# 07.net
KiCad netlist of a schematic drawn in Altium Designer
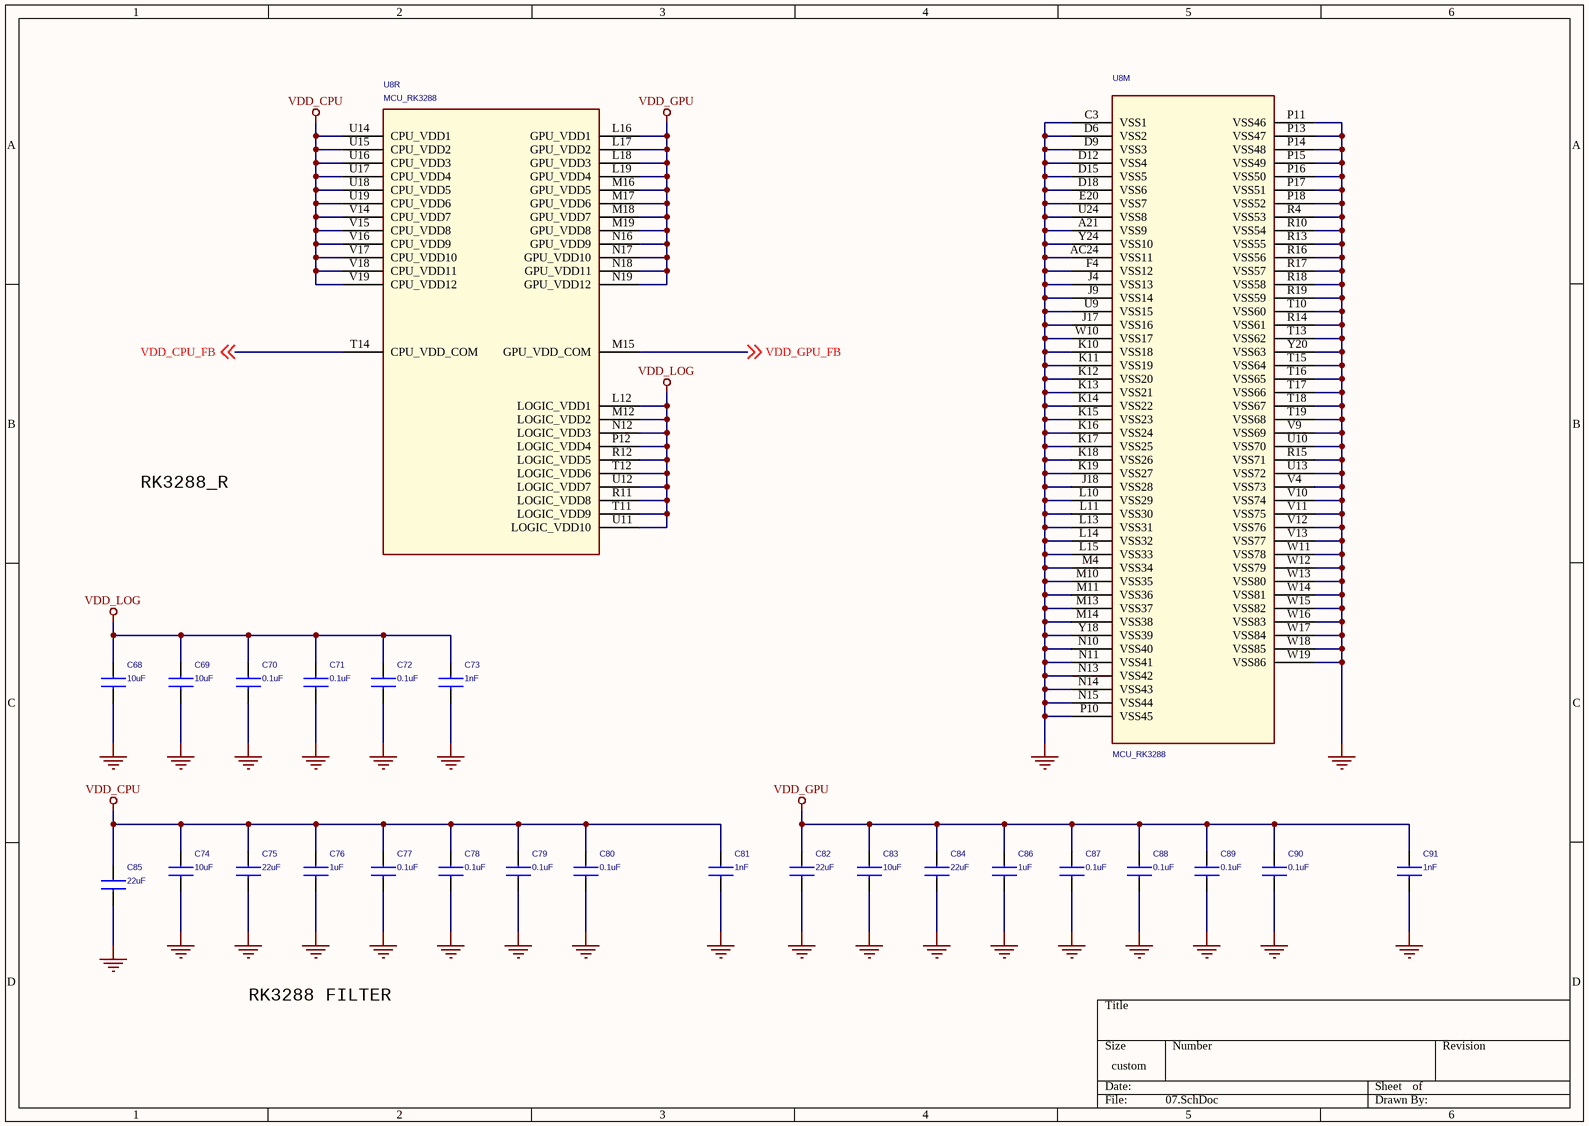
[diagram p0: 07.SchDoc]

(export (version "E")
  (design (tool "Eeschema 10.0.6"))
  (components
    (comp (ref "C68")
      (value "10uF")
      (footprint "C0603")
      (description "CAP,MLCC,10uF,+/-10%,X5R,6.3V,SMD0805")
      (libsource (lib "*") (part "CAP NP_Dup3"))
    )
    (comp (ref "C69") (value "10uF") (footprint "C0603") (libsource (lib "*") (part "CAP NP_Dup3")))
    (comp (ref "C70") (value "0.1uF") (footprint "C0603") (libsource (lib "*") (part "CAP NP_Dup3")))
    (comp (ref "C71") (value "0.1uF") (footprint "C0603") (libsource (lib "*") (part "CAP NP_Dup3")))
    (comp (ref "C72") (value "0.1uF") (footprint "C0603") (libsource (lib "*") (part "CAP NP_Dup3")))
    (comp (ref "C73") (value "1nF") (footprint "C0603") (libsource (lib "*") (part "CAP NP_Dup3")))
    (comp (ref "C74") (value "10uF") (footprint "C0603") (libsource (lib "*") (part "CAP NP_Dup3")))
    (comp (ref "C75") (value "22uF") (footprint "C0603") (libsource (lib "*") (part "CAP NP_Dup3")))
    (comp (ref "C76") (value "1uF") (footprint "C0603") (libsource (lib "*") (part "CAP NP_Dup3")))
    (comp (ref "C77") (value "0.1uF") (footprint "C0603") (libsource (lib "*") (part "CAP NP_Dup3")))
    (comp (ref "C78") (value "0.1uF") (footprint "C0603") (libsource (lib "*") (part "CAP NP_Dup3")))
    (comp (ref "C79") (value "0.1uF") (footprint "C0603") (libsource (lib "*") (part "CAP NP_Dup3")))
    (comp (ref "C80") (value "0.1uF") (footprint "C0603") (libsource (lib "*") (part "CAP NP_Dup3")))
    (comp (ref "C81") (value "1nF") (footprint "C0603") (libsource (lib "*") (part "CAP NP_Dup3")))
    (comp (ref "C82") (value "22uF") (footprint "C0603") (libsource (lib "*") (part "CAP NP_Dup3")))
    (comp (ref "C83")
      (value "10uF")
      (footprint "C0603")
      (description "CAP,MLCC,10uF,+/-10%,X5R,6.3V,SMD0805")
      (libsource (lib "*") (part "CAP NP_Dup3"))
    )
    (comp (ref "C84") (value "22uF") (footprint "C0603") (libsource (lib "*") (part "CAP NP_Dup3")))
    (comp (ref "C85")
      (value "22uF")
      (footprint "C0603")
      (description "CAP,MLCC,47uF,+/-10%,X5R,4V,SMD1210")
      (libsource (lib "*") (part "CAP NP_Dup3"))
    )
    (comp (ref "C86") (value "1uF") (footprint "C0603") (libsource (lib "*") (part "CAP NP_Dup3")))
    (comp (ref "C87") (value "0.1uF") (footprint "C0603") (libsource (lib "*") (part "CAP NP_Dup3")))
    (comp (ref "C88") (value "0.1uF") (footprint "C0603") (libsource (lib "*") (part "CAP NP_Dup3")))
    (comp (ref "C89") (value "0.1uF") (footprint "C0603") (libsource (lib "*") (part "CAP NP_Dup3")))
    (comp (ref "C90") (value "0.1uF") (footprint "C0603") (libsource (lib "*") (part "CAP NP_Dup3")))
    (comp (ref "C91") (value "1nF") (footprint "C0603") (libsource (lib "*") (part "CAP NP_Dup3")))
    (comp (ref "U8")
      (value "MCU_RK3288")
      (footprint "BGA453-19X19")
      (libsource (lib "*") (part "MCU_RK3288_3"))
    )
  )
  (nets
    (net (code "1") (name "GND") (class "Default")
      (node (ref "C68") (pin "1") (pinfunction "1_1") (pintype "passive"))
      (node (ref "C69") (pin "2") (pinfunction "2_2") (pintype "passive"))
      (node (ref "C70") (pin "2") (pinfunction "2_2") (pintype "passive"))
      (node (ref "C71") (pin "2") (pinfunction "2_2") (pintype "passive"))
      (node (ref "C72") (pin "2") (pinfunction "2_2") (pintype "passive"))
      (node (ref "C73") (pin "2") (pinfunction "2_2") (pintype "passive"))
      (node (ref "C74") (pin "1") (pinfunction "1_1") (pintype "passive"))
      (node (ref "C75") (pin "1") (pinfunction "1_1") (pintype "passive"))
      (node (ref "C76") (pin "2") (pinfunction "2_2") (pintype "passive"))
      (node (ref "C77") (pin "2") (pinfunction "2_2") (pintype "passive"))
      (node (ref "C78") (pin "2") (pinfunction "2_2") (pintype "passive"))
      (node (ref "C79") (pin "2") (pinfunction "2_2") (pintype "passive"))
      (node (ref "C80") (pin "2") (pinfunction "2_2") (pintype "passive"))
      (node (ref "C81") (pin "2") (pinfunction "2_2") (pintype "passive"))
      (node (ref "C82") (pin "1") (pinfunction "1_1") (pintype "passive"))
      (node (ref "C83") (pin "1") (pinfunction "1_1") (pintype "passive"))
      (node (ref "C84") (pin "1") (pinfunction "1_1") (pintype "passive"))
      (node (ref "C85") (pin "2") (pinfunction "2_2") (pintype "passive"))
      (node (ref "C86") (pin "2") (pinfunction "2_2") (pintype "passive"))
      (node (ref "C87") (pin "2") (pinfunction "2_2") (pintype "passive"))
      (node (ref "C88") (pin "2") (pinfunction "2_2") (pintype "passive"))
      (node (ref "C89") (pin "2") (pinfunction "2_2") (pintype "passive"))
      (node (ref "C90") (pin "2") (pinfunction "2_2") (pintype "passive"))
      (node (ref "C91") (pin "2") (pinfunction "2_2") (pintype "passive"))
      (node (ref "U8") (pin "A21") (pinfunction "VSS9_A21") (pintype "power_in"))
      (node (ref "U8") (pin "AC24") (pinfunction "VSS11_AC24") (pintype "power_in"))
      (node (ref "U8") (pin "C3") (pinfunction "VSS1_C3") (pintype "power_in"))
      (node (ref "U8") (pin "D12") (pinfunction "VSS4_D12") (pintype "power_in"))
      (node (ref "U8") (pin "D15") (pinfunction "VSS5_D15") (pintype "power_in"))
      (node (ref "U8") (pin "D18") (pinfunction "VSS6_D18") (pintype "power_in"))
      (node (ref "U8") (pin "D6") (pinfunction "VSS2_D6") (pintype "power_in"))
      (node (ref "U8") (pin "D9") (pinfunction "VSS3_D9") (pintype "power_in"))
      (node (ref "U8") (pin "E20") (pinfunction "VSS7_E20") (pintype "power_in"))
      (node (ref "U8") (pin "F4") (pinfunction "VSS12_F4") (pintype "power_in"))
      (node (ref "U8") (pin "J17") (pinfunction "VSS16_J17") (pintype "power_in"))
      (node (ref "U8") (pin "J18") (pinfunction "VSS28_J18") (pintype "power_in"))
      (node (ref "U8") (pin "J4") (pinfunction "VSS13_J4") (pintype "power_in"))
      (node (ref "U8") (pin "J9") (pinfunction "VSS14_J9") (pintype "power_in"))
      (node (ref "U8") (pin "K10") (pinfunction "VSS18_K10") (pintype "power_in"))
      (node (ref "U8") (pin "K11") (pinfunction "VSS19_K11") (pintype "power_in"))
      (node (ref "U8") (pin "K12") (pinfunction "VSS20_K12") (pintype "power_in"))
      (node (ref "U8") (pin "K13") (pinfunction "VSS21_K13") (pintype "power_in"))
      (node (ref "U8") (pin "K14") (pinfunction "VSS22_K14") (pintype "power_in"))
      (node (ref "U8") (pin "K15") (pinfunction "VSS23_K15") (pintype "power_in"))
      (node (ref "U8") (pin "K16") (pinfunction "VSS24_K16") (pintype "power_in"))
      (node (ref "U8") (pin "K17") (pinfunction "VSS25_K17") (pintype "power_in"))
      (node (ref "U8") (pin "K18") (pinfunction "VSS26_K18") (pintype "power_in"))
      (node (ref "U8") (pin "K19") (pinfunction "VSS27_K19") (pintype "power_in"))
      (node (ref "U8") (pin "L10") (pinfunction "VSS29_L10") (pintype "power_in"))
      (node (ref "U8") (pin "L11") (pinfunction "VSS30_L11") (pintype "power_in"))
      (node (ref "U8") (pin "L13") (pinfunction "VSS31_L13") (pintype "power_in"))
      (node (ref "U8") (pin "L14") (pinfunction "VSS32_L14") (pintype "power_in"))
      (node (ref "U8") (pin "L15") (pinfunction "VSS33_L15") (pintype "power_in"))
      (node (ref "U8") (pin "M10") (pinfunction "VSS35_M10") (pintype "power_in"))
      (node (ref "U8") (pin "M11") (pinfunction "VSS36_M11") (pintype "power_in"))
      (node (ref "U8") (pin "M13") (pinfunction "VSS37_M13") (pintype "power_in"))
      (node (ref "U8") (pin "M14") (pinfunction "VSS38_M14") (pintype "power_in"))
      (node (ref "U8") (pin "M4") (pinfunction "VSS34_M4") (pintype "power_in"))
      (node (ref "U8") (pin "N10") (pinfunction "VSS40_N10") (pintype "power_in"))
      (node (ref "U8") (pin "N11") (pinfunction "VSS41_N11") (pintype "power_in"))
      (node (ref "U8") (pin "N13") (pinfunction "VSS42_N13") (pintype "power_in"))
      (node (ref "U8") (pin "N14") (pinfunction "VSS43_N14") (pintype "power_in"))
      (node (ref "U8") (pin "N15") (pinfunction "VSS44_N15") (pintype "power_in"))
      (node (ref "U8") (pin "P10") (pinfunction "VSS45_P10") (pintype "power_in"))
      (node (ref "U8") (pin "P11") (pinfunction "VSS46_P11") (pintype "power_in"))
      (node (ref "U8") (pin "P13") (pinfunction "VSS47_P13") (pintype "power_in"))
      (node (ref "U8") (pin "P14") (pinfunction "VSS48_P14") (pintype "power_in"))
      (node (ref "U8") (pin "P15") (pinfunction "VSS49_P15") (pintype "power_in"))
      (node (ref "U8") (pin "P16") (pinfunction "VSS50_P16") (pintype "power_in"))
      (node (ref "U8") (pin "P17") (pinfunction "VSS51_P17") (pintype "power_in"))
      (node (ref "U8") (pin "P18") (pinfunction "VSS52_P18") (pintype "power_in"))
      (node (ref "U8") (pin "R10") (pinfunction "VSS54_R10") (pintype "power_in"))
      (node (ref "U8") (pin "R13") (pinfunction "VSS55_R13") (pintype "power_in"))
      (node (ref "U8") (pin "R14") (pinfunction "VSS61_R14") (pintype "power_in"))
      (node (ref "U8") (pin "R15") (pinfunction "VSS71_R15") (pintype "power_in"))
      (node (ref "U8") (pin "R16") (pinfunction "VSS56_R16") (pintype "power_in"))
      (node (ref "U8") (pin "R17") (pinfunction "VSS57_R17") (pintype "power_in"))
      (node (ref "U8") (pin "R18") (pinfunction "VSS58_R18") (pintype "power_in"))
      (node (ref "U8") (pin "R19") (pinfunction "VSS59_R19") (pintype "power_in"))
      (node (ref "U8") (pin "R4") (pinfunction "VSS53_R4") (pintype "power_in"))
      (node (ref "U8") (pin "T10") (pinfunction "VSS60_T10") (pintype "power_in"))
      (node (ref "U8") (pin "T13") (pinfunction "VSS62_T13") (pintype "power_in"))
      (node (ref "U8") (pin "T15") (pinfunction "VSS64_T15") (pintype "power_in"))
      (node (ref "U8") (pin "T16") (pinfunction "VSS65_T16") (pintype "power_in"))
      (node (ref "U8") (pin "T17") (pinfunction "VSS66_T17") (pintype "power_in"))
      (node (ref "U8") (pin "T18") (pinfunction "VSS67_T18") (pintype "power_in"))
      (node (ref "U8") (pin "T19") (pinfunction "VSS68_T19") (pintype "power_in"))
      (node (ref "U8") (pin "U10") (pinfunction "VSS70_U10") (pintype "power_in"))
      (node (ref "U8") (pin "U13") (pinfunction "VSS72_U13") (pintype "power_in"))
      (node (ref "U8") (pin "U24") (pinfunction "VSS8_U24") (pintype "power_in"))
      (node (ref "U8") (pin "U9") (pinfunction "VSS15_U9") (pintype "power_in"))
      (node (ref "U8") (pin "V10") (pinfunction "VSS74_V10") (pintype "power_in"))
      (node (ref "U8") (pin "V11") (pinfunction "VSS75_V11") (pintype "power_in"))
      (node (ref "U8") (pin "V12") (pinfunction "VSS76_V12") (pintype "power_in"))
      (node (ref "U8") (pin "V13") (pinfunction "VSS77_V13") (pintype "power_in"))
      (node (ref "U8") (pin "V4") (pinfunction "VSS73_V4") (pintype "power_in"))
      (node (ref "U8") (pin "V9") (pinfunction "VSS69_V9") (pintype "power_in"))
      (node (ref "U8") (pin "W10") (pinfunction "VSS17_W10") (pintype "power_in"))
      (node (ref "U8") (pin "W11") (pinfunction "VSS78_W11") (pintype "power_in"))
      (node (ref "U8") (pin "W12") (pinfunction "VSS79_W12") (pintype "power_in"))
      (node (ref "U8") (pin "W13") (pinfunction "VSS80_W13") (pintype "power_in"))
      (node (ref "U8") (pin "W14") (pinfunction "VSS81_W14") (pintype "power_in"))
      (node (ref "U8") (pin "W15") (pinfunction "VSS82_W15") (pintype "power_in"))
      (node (ref "U8") (pin "W16") (pinfunction "VSS83_W16") (pintype "power_in"))
      (node (ref "U8") (pin "W17") (pinfunction "VSS84_W17") (pintype "power_in"))
      (node (ref "U8") (pin "W18") (pinfunction "VSS85_W18") (pintype "power_in"))
      (node (ref "U8") (pin "W19") (pinfunction "VSS86_W19") (pintype "power_in"))
      (node (ref "U8") (pin "Y18") (pinfunction "VSS39_Y18") (pintype "power_in"))
      (node (ref "U8") (pin "Y20") (pinfunction "VSS63_Y20") (pintype "power_in"))
      (node (ref "U8") (pin "Y24") (pinfunction "VSS10_Y24") (pintype "power_in"))
    )
    (net (code "2") (name "VDD_CPU") (class "Default")
      (node (ref "C74") (pin "2") (pinfunction "2_2") (pintype "passive"))
      (node (ref "C75") (pin "2") (pinfunction "2_2") (pintype "passive"))
      (node (ref "C76") (pin "1") (pinfunction "1_1") (pintype "passive"))
      (node (ref "C77") (pin "1") (pinfunction "1_1") (pintype "passive"))
      (node (ref "C78") (pin "1") (pinfunction "1_1") (pintype "passive"))
      (node (ref "C79") (pin "1") (pinfunction "1_1") (pintype "passive"))
      (node (ref "C80") (pin "1") (pinfunction "1_1") (pintype "passive"))
      (node (ref "C81") (pin "1") (pinfunction "1_1") (pintype "passive"))
      (node (ref "C85") (pin "1") (pinfunction "1_1") (pintype "passive"))
      (node (ref "U8") (pin "U14") (pinfunction "CPU_VDD1_U14") (pintype "power_in"))
      (node (ref "U8") (pin "U15") (pinfunction "CPU_VDD2_U15") (pintype "power_in"))
      (node (ref "U8") (pin "U16") (pinfunction "CPU_VDD3_U16") (pintype "power_in"))
      (node (ref "U8") (pin "U17") (pinfunction "CPU_VDD4_U17") (pintype "power_in"))
      (node (ref "U8") (pin "U18") (pinfunction "CPU_VDD5_U18") (pintype "power_in"))
      (node (ref "U8") (pin "U19") (pinfunction "CPU_VDD6_U19") (pintype "power_in"))
      (node (ref "U8") (pin "V14") (pinfunction "CPU_VDD7_V14") (pintype "power_in"))
      (node (ref "U8") (pin "V15") (pinfunction "CPU_VDD8_V15") (pintype "power_in"))
      (node (ref "U8") (pin "V16") (pinfunction "CPU_VDD9_V16") (pintype "power_in"))
      (node (ref "U8") (pin "V17") (pinfunction "CPU_VDD10_V17") (pintype "power_in"))
      (node (ref "U8") (pin "V18") (pinfunction "CPU_VDD11_V18") (pintype "power_in"))
      (node (ref "U8") (pin "V19") (pinfunction "CPU_VDD12_V19") (pintype "power_in"))
    )
    (net (code "3") (name "VDD_CPU_FB") (class "Default")
      (node (ref "U8") (pin "T14") (pinfunction "CPU_VDD_COM_T14") (pintype "passive"))
    )
    (net (code "4") (name "VDD_GPU") (class "Default")
      (node (ref "C82") (pin "2") (pinfunction "2_2") (pintype "passive"))
      (node (ref "C83") (pin "2") (pinfunction "2_2") (pintype "passive"))
      (node (ref "C84") (pin "2") (pinfunction "2_2") (pintype "passive"))
      (node (ref "C86") (pin "1") (pinfunction "1_1") (pintype "passive"))
      (node (ref "C87") (pin "1") (pinfunction "1_1") (pintype "passive"))
      (node (ref "C88") (pin "1") (pinfunction "1_1") (pintype "passive"))
      (node (ref "C89") (pin "1") (pinfunction "1_1") (pintype "passive"))
      (node (ref "C90") (pin "1") (pinfunction "1_1") (pintype "passive"))
      (node (ref "C91") (pin "1") (pinfunction "1_1") (pintype "passive"))
      (node (ref "U8") (pin "L16") (pinfunction "GPU_VDD1_L16") (pintype "power_in"))
      (node (ref "U8") (pin "L17") (pinfunction "GPU_VDD2_L17") (pintype "power_in"))
      (node (ref "U8") (pin "L18") (pinfunction "GPU_VDD3_L18") (pintype "power_in"))
      (node (ref "U8") (pin "L19") (pinfunction "GPU_VDD4_L19") (pintype "power_in"))
      (node (ref "U8") (pin "M16") (pinfunction "GPU_VDD5_M16") (pintype "power_in"))
      (node (ref "U8") (pin "M17") (pinfunction "GPU_VDD6_M17") (pintype "power_in"))
      (node (ref "U8") (pin "M18") (pinfunction "GPU_VDD7_M18") (pintype "power_in"))
      (node (ref "U8") (pin "M19") (pinfunction "GPU_VDD8_M19") (pintype "power_in"))
      (node (ref "U8") (pin "N16") (pinfunction "GPU_VDD9_N16") (pintype "power_in"))
      (node (ref "U8") (pin "N17") (pinfunction "GPU_VDD10_N17") (pintype "power_in"))
      (node (ref "U8") (pin "N18") (pinfunction "GPU_VDD11_N18") (pintype "power_in"))
      (node (ref "U8") (pin "N19") (pinfunction "GPU_VDD12_N19") (pintype "power_in"))
    )
    (net (code "5") (name "VDD_GPU_FB") (class "Default")
      (node (ref "U8") (pin "M15") (pinfunction "GPU_VDD_COM_M15") (pintype "passive"))
    )
    (net (code "6") (name "VDD_LOG") (class "Default")
      (node (ref "C68") (pin "2") (pinfunction "2_2") (pintype "passive"))
      (node (ref "C69") (pin "1") (pinfunction "1_1") (pintype "passive"))
      (node (ref "C70") (pin "1") (pinfunction "1_1") (pintype "passive"))
      (node (ref "C71") (pin "1") (pinfunction "1_1") (pintype "passive"))
      (node (ref "C72") (pin "1") (pinfunction "1_1") (pintype "passive"))
      (node (ref "C73") (pin "1") (pinfunction "1_1") (pintype "passive"))
      (node (ref "U8") (pin "L12") (pinfunction "LOGIC_VDD1_L12") (pintype "power_in"))
      (node (ref "U8") (pin "M12") (pinfunction "LOGIC_VDD2_M12") (pintype "power_in"))
      (node (ref "U8") (pin "N12") (pinfunction "LOGIC_VDD3_N12") (pintype "power_in"))
      (node (ref "U8") (pin "P12") (pinfunction "LOGIC_VDD4_P12") (pintype "power_in"))
      (node (ref "U8") (pin "R11") (pinfunction "LOGIC_VDD8_R11") (pintype "power_in"))
      (node (ref "U8") (pin "R12") (pinfunction "LOGIC_VDD5_R12") (pintype "power_in"))
      (node (ref "U8") (pin "T11") (pinfunction "LOGIC_VDD9_T11") (pintype "power_in"))
      (node (ref "U8") (pin "T12") (pinfunction "LOGIC_VDD6_T12") (pintype "power_in"))
      (node (ref "U8") (pin "U11") (pinfunction "LOGIC_VDD10_U11") (pintype "power_in"))
      (node (ref "U8") (pin "U12") (pinfunction "LOGIC_VDD7_U12") (pintype "power_in"))
    )
  )
)
